# ft231x-breakout-v11-openSX70version.net
KiCad netlist of a schematic drawn in EAGLE
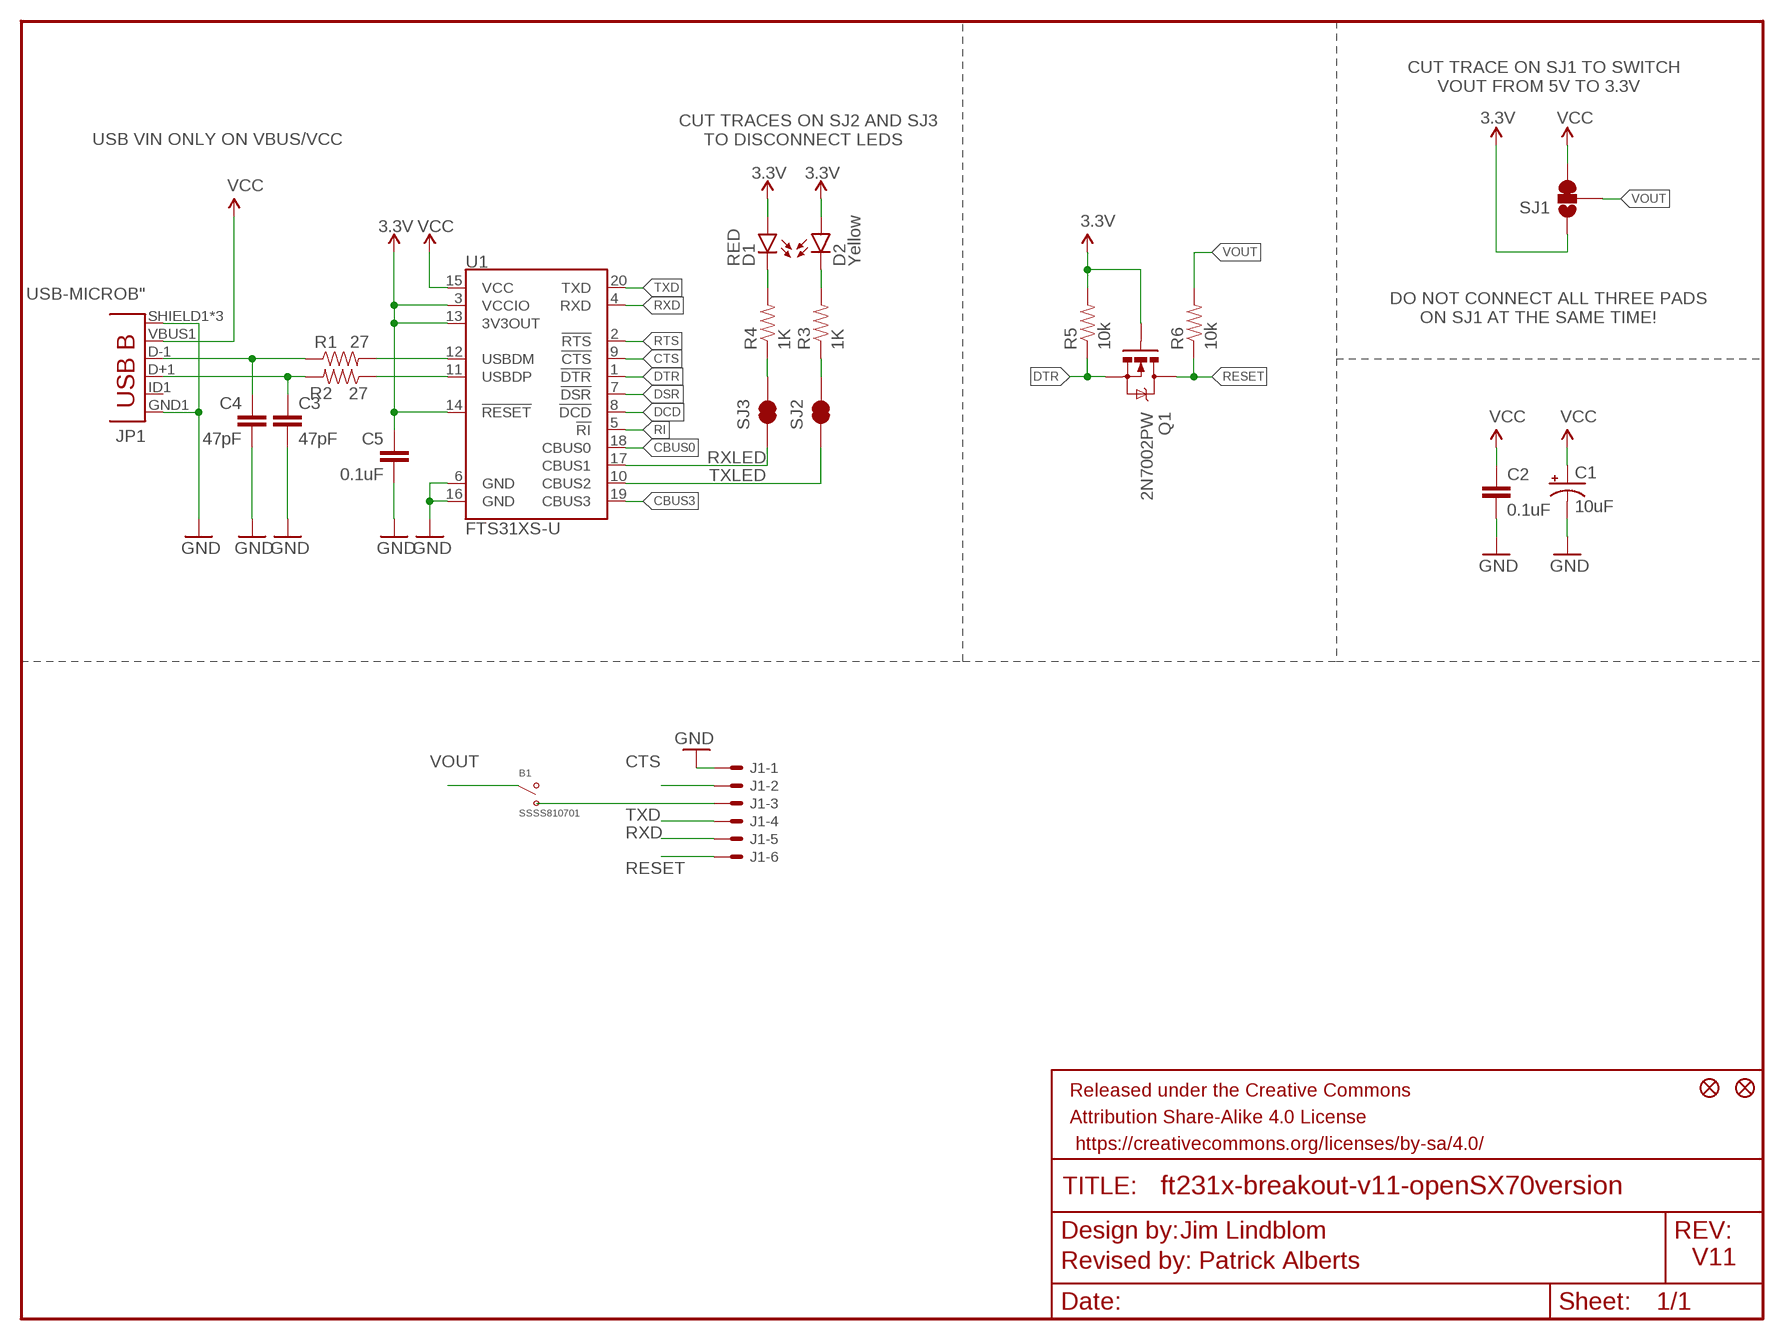
[diagram p0: schematic, sheet 1]

(export (version "E")
  (design (tool "Eeschema 10.0.6"))
  (components
    (comp (ref "B1")
      (value "SSSS810701")
      (footprint "eagle-import:SSSS810701")
      (fields (field (name "MF") "ALPS"))
      (libsource (lib "eagle-import") (part "SSSS810701"))
    )
    (comp (ref "C1")
      (value "10uF")
      (footprint "eagle-import:EIA3216")
      (libsource (lib "eagle-import") (part "10UF-16V-10%(TANT)"))
    )
    (comp (ref "C2")
      (value "0.1uF")
      (footprint "eagle-import:0603-CAP")
      (libsource (lib "eagle-import") (part "0.1UF-25V(+80/-20%)(0603)"))
    )
    (comp (ref "C3")
      (value "47pF")
      (footprint "eagle-import:0603-CAP")
      (libsource (lib "eagle-import") (part "47PF-50V-5%(0603)"))
    )
    (comp (ref "C4")
      (value "47pF")
      (footprint "eagle-import:0603-CAP")
      (libsource (lib "eagle-import") (part "47PF-50V-5%(0603)"))
    )
    (comp (ref "C5")
      (value "0.1uF")
      (footprint "eagle-import:0603-CAP")
      (libsource (lib "eagle-import") (part "0.1UF-25V(+80/-20%)(0603)"))
    )
    (comp (ref "D1")
      (value "RED")
      (footprint "eagle-import:LED-0603")
      (libsource (lib "eagle-import") (part "LED-RED0603"))
    )
    (comp (ref "D2")
      (value "Yellow")
      (footprint "eagle-import:LED-0603")
      (libsource (lib "eagle-import") (part "LED-YELLOW0603"))
    )
    (comp (ref "FRAME1")
      (value "FRAME-LETTER")
      (footprint "eagle-import:CREATIVE_COMMONS")
      (libsource (lib "eagle-import") (part "FRAME-LETTER"))
    )
    (comp (ref "J1")
      (value "XF2L-0625-1")
      (footprint "eagle-import:XF2L-0625-1")
      (fields (field (name "MF") "OMRON COMPONENTS USA"))
      (libsource (lib "eagle-import") (part "XF2-06?25-1L"))
    )
    (comp (ref "JP1")
      (value "USB-MICROB\"")
      (footprint "eagle-import:USB-B-MICRO-SMD_V03")
      (libsource (lib "eagle-import") (part "USB-MICROB{dblquote}"))
    )
    (comp (ref "JP5")
      (value "FIDUCIAL1X2")
      (footprint "eagle-import:FIDUCIAL-1X2")
      (libsource (lib "eagle-import") (part "FIDUCIAL1X2"))
    )
    (comp (ref "JP6")
      (value "FIDUCIAL1X2")
      (footprint "eagle-import:FIDUCIAL-1X2")
      (libsource (lib "eagle-import") (part "FIDUCIAL1X2"))
    )
    (comp (ref "Q1")
      (value "2N7002PW")
      (footprint "eagle-import:SOT323")
      (libsource (lib "eagle-import") (part "MOSFET-NCHANNEL2N7002PW"))
    )
    (comp (ref "R1")
      (value "27")
      (footprint "eagle-import:0603-RES")
      (libsource (lib "eagle-import") (part "27OHM1/10W1%(0603)0603-RES"))
    )
    (comp (ref "R2")
      (value "27")
      (footprint "eagle-import:0603-RES")
      (libsource (lib "eagle-import") (part "27OHM1/10W1%(0603)0603-RES"))
    )
    (comp (ref "R3")
      (value "1K")
      (footprint "eagle-import:0603-RES")
      (libsource (lib "eagle-import") (part "1KOHM-1/10W-1%(0603)"))
    )
    (comp (ref "R4")
      (value "1K")
      (footprint "eagle-import:0603-RES")
      (libsource (lib "eagle-import") (part "1KOHM-1/10W-1%(0603)"))
    )
    (comp (ref "R5")
      (value "10k")
      (footprint "eagle-import:0603-RES@1")
      (libsource (lib "eagle-import") (part "10KOHM1/10W1%(0603)0603"))
    )
    (comp (ref "R6")
      (value "10k")
      (footprint "eagle-import:0603-RES@1")
      (libsource (lib "eagle-import") (part "10KOHM1/10W1%(0603)0603"))
    )
    (comp (ref "SJ1")
      (value "SOLDERJUMPER_2WAYS")
      (footprint "eagle-import:SJ_3")
      (libsource (lib "eagle-import") (part "SOLDERJUMPER_2WAYS"))
    )
    (comp (ref "SJ2")
      (value "TXLED")
      (footprint "eagle-import:SJ_2S-TRACE")
      (libsource (lib "eagle-import") (part "SOLDERJUMPERTRACE"))
    )
    (comp (ref "SJ3")
      (value "RXLED")
      (footprint "eagle-import:PAD-JUMPER-2-NC_BY_TRACE_YES_SILK")
      (libsource (lib "eagle-import") (part "JUMPER-PAD-2-NC_BY_TRACE"))
    )
    (comp (ref "U1")
      (value "FTS31XS-U")
      (footprint "eagle-import:SSOP20_L")
      (libsource (lib "eagle-import") (part "FT231XS"))
    )
  )
  (nets
    (net (code "1") (name "/RXLED") (class "Default")
      (node (ref "SJ3") (pin "1") (pinfunction "1_1") (pintype "passive"))
      (node (ref "U1") (pin "17") (pinfunction "CBUS1_17") (pintype "bidirectional"))
    )
    (net (code "2") (name "/TXLED") (class "Default")
      (node (ref "SJ2") (pin "1") (pinfunction "1_1") (pintype "passive"))
      (node (ref "U1") (pin "10") (pinfunction "CBUS2_10") (pintype "bidirectional"))
    )
    (net (code "3") (name "3.3V") (class "Default")
      (node (ref "C5") (pin "1") (pinfunction "1_1") (pintype "passive"))
      (node (ref "D1") (pin "A") (pinfunction "A_A") (pintype "passive"))
      (node (ref "D2") (pin "A") (pinfunction "A_A") (pintype "passive"))
      (node (ref "Q1") (pin "1") (pinfunction "G_1") (pintype "passive"))
      (node (ref "R5") (pin "2") (pinfunction "2_2") (pintype "passive"))
      (node (ref "SJ1") (pin "1") (pinfunction "1_1") (pintype "passive"))
      (node (ref "U1") (pin "13") (pinfunction "3V3OUT_13") (pintype "bidirectional"))
      (node (ref "U1") (pin "14") (pinfunction "~{RESET}_14") (pintype "bidirectional"))
      (node (ref "U1") (pin "3") (pinfunction "VCCIO_3") (pintype "bidirectional"))
    )
    (net (code "4") (name "CBUS0") (class "Default")
      (node (ref "U1") (pin "18") (pinfunction "CBUS0_18") (pintype "bidirectional"))
    )
    (net (code "5") (name "CBUS3") (class "Default")
      (node (ref "U1") (pin "19") (pinfunction "CBUS3_19") (pintype "bidirectional"))
    )
    (net (code "6") (name "CTS") (class "Default")
      (node (ref "J1") (pin "2") (pinfunction "MS_2") (pintype "passive"))
      (node (ref "U1") (pin "9") (pinfunction "~{CTS}_9") (pintype "bidirectional"))
    )
    (net (code "7") (name "DCD") (class "Default")
      (node (ref "U1") (pin "8") (pinfunction "~{DCD}_8") (pintype "bidirectional"))
    )
    (net (code "8") (name "DSR") (class "Default")
      (node (ref "U1") (pin "7") (pinfunction "~{DSR}_7") (pintype "bidirectional"))
    )
    (net (code "9") (name "DTR") (class "Default")
      (node (ref "Q1") (pin "2") (pinfunction "S_2") (pintype "passive"))
      (node (ref "R5") (pin "1") (pinfunction "1_1") (pintype "passive"))
      (node (ref "U1") (pin "1") (pinfunction "~{DTR}_1") (pintype "bidirectional"))
    )
    (net (code "10") (name "GND") (class "Default")
      (node (ref "C1") (pin "C") (pinfunction "-_C") (pintype "passive"))
      (node (ref "C2") (pin "2") (pinfunction "2_2") (pintype "passive"))
      (node (ref "C3") (pin "2") (pinfunction "2_2") (pintype "passive"))
      (node (ref "C4") (pin "2") (pinfunction "2_2") (pintype "passive"))
      (node (ref "C5") (pin "2") (pinfunction "2_2") (pintype "passive"))
      (node (ref "J1") (pin "1") (pinfunction "MS_1") (pintype "passive"))
      (node (ref "JP1") (pin "GND1") (pinfunction "GND_GND1") (pintype "bidirectional"))
      (node (ref "JP1") (pin "SHIELD1") (pinfunction "SHIELD_SHIELD1") (pintype "bidirectional"))
      (node (ref "JP1") (pin "SHIELD2") (pinfunction "SHIELD_SHIELD2") (pintype "bidirectional"))
      (node (ref "JP1") (pin "SHIELD3") (pinfunction "SHIELD_SHIELD3") (pintype "bidirectional"))
      (node (ref "U1") (pin "16") (pinfunction "GND_16") (pintype "bidirectional"))
      (node (ref "U1") (pin "6") (pinfunction "GND_6") (pintype "bidirectional"))
    )
    (net (code "11") (name "Net-(B1-B)") (class "Default")
      (node (ref "B1") (pin "1") (pinfunction "B_1") (pintype "bidirectional"))
      (node (ref "J1") (pin "3") (pinfunction "MS_3") (pintype "passive"))
    )
    (net (code "12") (name "Net-(D1-PadC)") (class "Default")
      (node (ref "D1") (pin "C") (pinfunction "C_C") (pintype "passive"))
      (node (ref "R4") (pin "2") (pinfunction "2_2") (pintype "passive"))
    )
    (net (code "13") (name "Net-(D2-PadC)") (class "Default")
      (node (ref "D2") (pin "C") (pinfunction "C_C") (pintype "passive"))
      (node (ref "R3") (pin "2") (pinfunction "2_2") (pintype "passive"))
    )
    (net (code "14") (name "Net-(JP1-D+)") (class "Default")
      (node (ref "C3") (pin "1") (pinfunction "1_1") (pintype "passive"))
      (node (ref "JP1") (pin "D+1") (pinfunction "D+_D+1") (pintype "bidirectional"))
      (node (ref "R2") (pin "2") (pinfunction "2_2") (pintype "passive"))
    )
    (net (code "15") (name "Net-(JP1-D-)") (class "Default")
      (node (ref "C4") (pin "1") (pinfunction "1_1") (pintype "passive"))
      (node (ref "JP1") (pin "D-1") (pinfunction "D-_D-1") (pintype "bidirectional"))
      (node (ref "R1") (pin "1") (pinfunction "1_1") (pintype "passive"))
    )
    (net (code "16") (name "Net-(R3-Pad1)") (class "Default")
      (node (ref "R3") (pin "1") (pinfunction "1_1") (pintype "passive"))
      (node (ref "SJ2") (pin "2") (pinfunction "2_2") (pintype "passive"))
    )
    (net (code "17") (name "Net-(R4-Pad1)") (class "Default")
      (node (ref "R4") (pin "1") (pinfunction "1_1") (pintype "passive"))
      (node (ref "SJ3") (pin "2") (pinfunction "2_2") (pintype "passive"))
    )
    (net (code "18") (name "Net-(U1-USBDM)") (class "Default")
      (node (ref "R1") (pin "2") (pinfunction "2_2") (pintype "passive"))
      (node (ref "U1") (pin "12") (pinfunction "USBDM_12") (pintype "bidirectional"))
    )
    (net (code "19") (name "Net-(U1-USBDP)") (class "Default")
      (node (ref "R2") (pin "1") (pinfunction "1_1") (pintype "passive"))
      (node (ref "U1") (pin "11") (pinfunction "USBDP_11") (pintype "bidirectional"))
    )
    (net (code "20") (name "RESET") (class "Default")
      (node (ref "J1") (pin "6") (pinfunction "MS_6") (pintype "passive"))
      (node (ref "Q1") (pin "3") (pinfunction "D_3") (pintype "passive"))
      (node (ref "R6") (pin "1") (pinfunction "1_1") (pintype "passive"))
    )
    (net (code "21") (name "RI") (class "Default")
      (node (ref "U1") (pin "5") (pinfunction "~{RI}_5") (pintype "bidirectional"))
    )
    (net (code "22") (name "RTS") (class "Default")
      (node (ref "U1") (pin "2") (pinfunction "~{RTS}_2") (pintype "bidirectional"))
    )
    (net (code "23") (name "RXD") (class "Default")
      (node (ref "J1") (pin "5") (pinfunction "MS_5") (pintype "passive"))
      (node (ref "U1") (pin "4") (pinfunction "RXD_4") (pintype "bidirectional"))
    )
    (net (code "24") (name "TXD") (class "Default")
      (node (ref "J1") (pin "4") (pinfunction "MS_4") (pintype "passive"))
      (node (ref "U1") (pin "20") (pinfunction "TXD_20") (pintype "bidirectional"))
    )
    (net (code "25") (name "VCC") (class "Default")
      (node (ref "C1") (pin "A") (pinfunction "+_A") (pintype "passive"))
      (node (ref "C2") (pin "1") (pinfunction "1_1") (pintype "passive"))
      (node (ref "JP1") (pin "VBUS1") (pinfunction "VBUS_VBUS1") (pintype "bidirectional"))
      (node (ref "SJ1") (pin "3") (pinfunction "3_3") (pintype "passive"))
      (node (ref "U1") (pin "15") (pinfunction "VCC_15") (pintype "bidirectional"))
    )
    (net (code "26") (name "VOUT") (class "Default")
      (node (ref "B1") (pin "2") (pinfunction "COM_2") (pintype "bidirectional"))
      (node (ref "R6") (pin "2") (pinfunction "2_2") (pintype "passive"))
      (node (ref "SJ1") (pin "2") (pinfunction "2_2") (pintype "passive"))
    )
    (net (code "27") (name "unconnected-(B1-A-Pad3)") (class "Default")
      (node (ref "B1") (pin "3") (pinfunction "A_3") (pintype "bidirectional"))
    )
    (net (code "28") (name "unconnected-(JP1-USBID-PadID1)") (class "Default")
      (node (ref "JP1") (pin "ID1") (pinfunction "USBID_ID1") (pintype "bidirectional"))
    )
  )
)
